# JTAG.net
KiCad netlist of a schematic drawn in Altium Designer
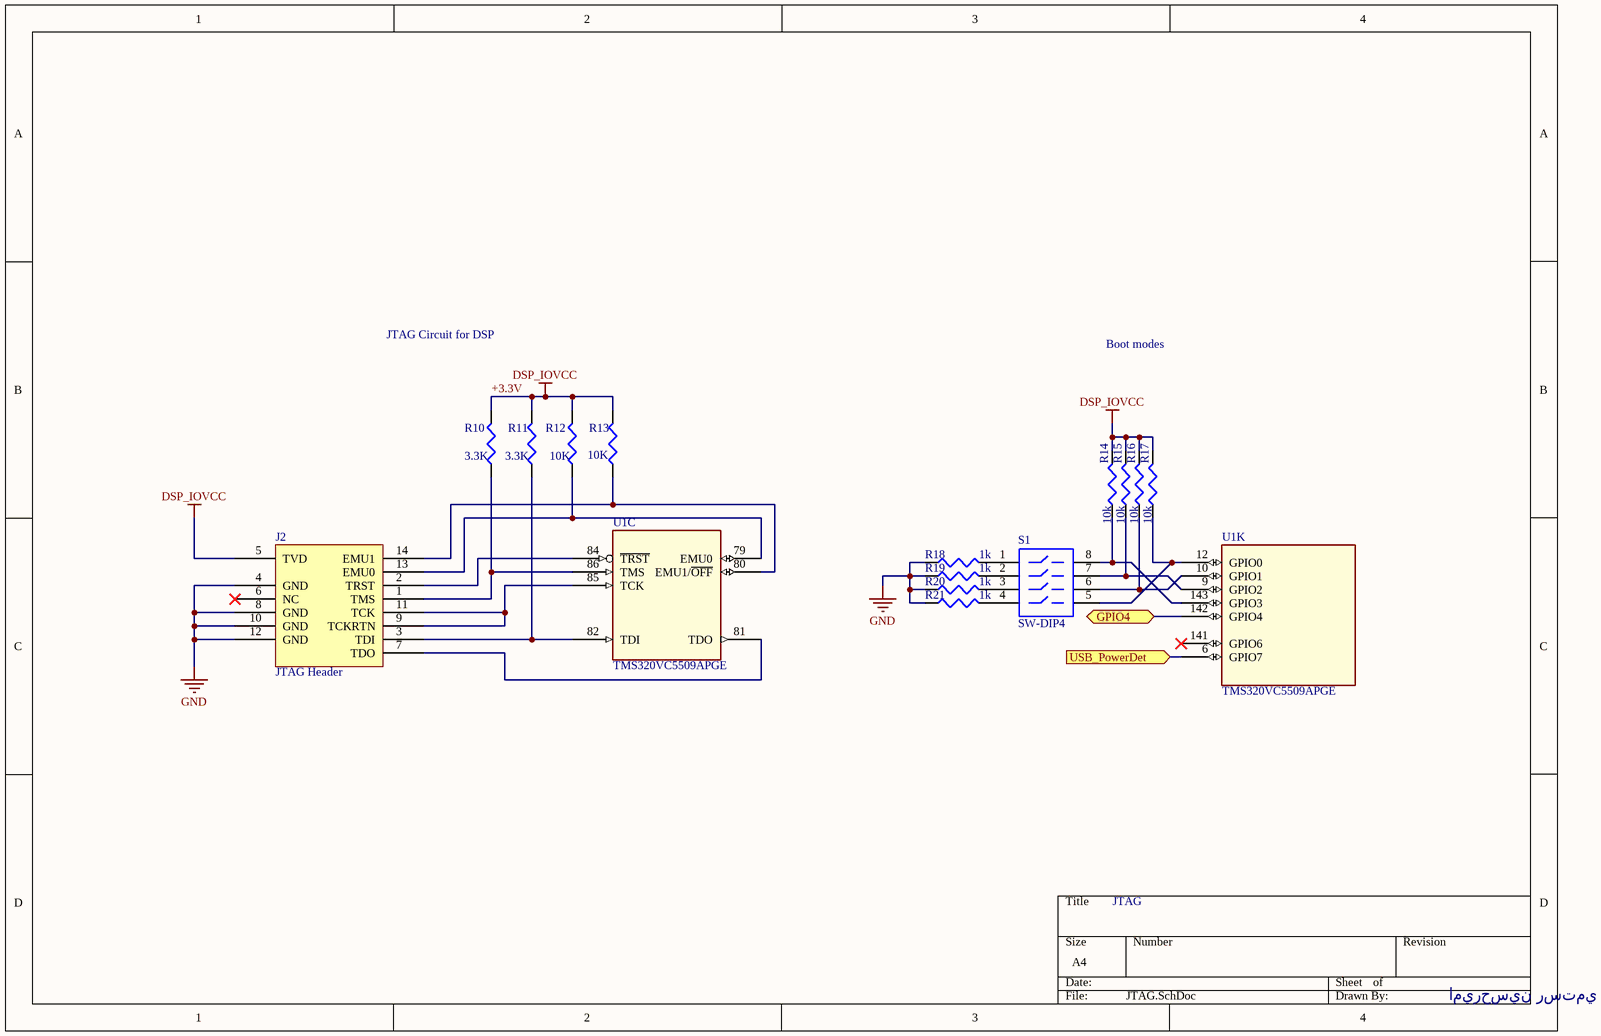
[diagram p0: JTAG.SchDoc]

(export (version "E")
  (design (tool "Eeschema 10.0.6"))
  (components
    (comp (ref "J2")
      (value "JTAG Header")
      (footprint "HDR2X7")
      (description "JTAG Header for DSP 5509")
      (libsource (lib "JTAG_Header") (part "JTAG Header"))
    )
    (comp (ref "R10")
      (value "3.3K")
      (footprint "J1-0603")
      (description "Resistor")
      (fields (field (name "Comment") "3.3k") (field (name "PUBLISHER") "Altium Limited"))
      (libsource (lib "Miscellaneous Devices") (part "Res3"))
    )
    (comp (ref "R11")
      (value "3.3K")
      (footprint "J1-0603")
      (description "Resistor")
      (fields (field (name "Comment") "3.3k") (field (name "PUBLISHER") "Altium Limited"))
      (libsource (lib "Miscellaneous Devices") (part "Res3"))
    )
    (comp (ref "R12")
      (value "10K")
      (footprint "J1-0603")
      (description "Resistor")
      (fields (field (name "Comment") "10k") (field (name "PUBLISHER") "Altium Limited"))
      (libsource (lib "Miscellaneous Devices") (part "Res3"))
    )
    (comp (ref "R13")
      (value "10K")
      (footprint "J1-0603")
      (description "Resistor")
      (fields (field (name "Comment") "10k") (field (name "PUBLISHER") "Altium Limited"))
      (libsource (lib "Miscellaneous Devices") (part "Res3"))
    )
    (comp (ref "R14")
      (value "10k")
      (footprint "J1-0603")
      (description "Resistor")
      (fields (field (name "PUBLISHER") "Altium Limited"))
      (libsource (lib "Miscellaneous Devices") (part "Res3"))
    )
    (comp (ref "R15")
      (value "10k")
      (footprint "J1-0603")
      (description "Resistor")
      (fields (field (name "PUBLISHER") "Altium Limited"))
      (libsource (lib "Miscellaneous Devices") (part "Res3"))
    )
    (comp (ref "R16")
      (value "10k")
      (footprint "J1-0603")
      (description "Resistor")
      (fields (field (name "PUBLISHER") "Altium Limited"))
      (libsource (lib "Miscellaneous Devices") (part "Res3"))
    )
    (comp (ref "R17")
      (value "10k")
      (footprint "J1-0603")
      (description "Resistor")
      (fields (field (name "PUBLISHER") "Altium Limited"))
      (libsource (lib "Miscellaneous Devices") (part "Res3"))
    )
    (comp (ref "R18")
      (value "1k")
      (footprint "J1-0603")
      (description "Resistor")
      (fields (field (name "PUBLISHER") "Altium Limited"))
      (libsource (lib "Miscellaneous Devices") (part "Res3"))
    )
    (comp (ref "R19")
      (value "1k")
      (footprint "J1-0603")
      (description "Resistor")
      (fields (field (name "PUBLISHER") "Altium Limited"))
      (libsource (lib "Miscellaneous Devices") (part "Res3"))
    )
    (comp (ref "R20")
      (value "1k")
      (footprint "J1-0603")
      (description "Resistor")
      (fields (field (name "PUBLISHER") "Altium Limited"))
      (libsource (lib "Miscellaneous Devices") (part "Res3"))
    )
    (comp (ref "R21")
      (value "1k")
      (footprint "J1-0603")
      (description "Resistor")
      (fields (field (name "PUBLISHER") "Altium Limited"))
      (libsource (lib "Miscellaneous Devices") (part "Res3"))
    )
    (comp (ref "S1")
      (value "SW-DIP4")
      (footprint "DIP-8")
      (description "DIP Switch")
      (fields (field (name "PUBLISHER") "Altium Limited"))
      (libsource (lib "Miscellaneous Devices") (part "SW-DIP4"))
    )
    (comp (ref "U1")
      (value "TMS320VC5509APGE")
      (footprint "TMSVC5509APGA")
      (libsource (lib "TMSVC5509APGE") (part "TMS320VC5509APGE"))
    )
  )
  (nets
    (net (code "1") (name "/GPIO4") (class "Default")
      (node (ref "U1") (pin "142") (pinfunction "GPIO4_142") (pintype "bidirectional"))
    )
    (net (code "2") (name "/USB_PowerDet") (class "Default")
      (node (ref "U1") (pin "6") (pinfunction "GPIO7_6") (pintype "bidirectional"))
    )
    (net (code "3") (name "DSP_IOVCC") (class "Default")
      (node (ref "J2") (pin "5") (pinfunction "TVD_5") (pintype "passive"))
      (node (ref "R10") (pin "2") (pinfunction "2_2") (pintype "passive"))
      (node (ref "R11") (pin "2") (pinfunction "2_2") (pintype "passive"))
      (node (ref "R12") (pin "2") (pinfunction "2_2") (pintype "passive"))
      (node (ref "R13") (pin "2") (pinfunction "2_2") (pintype "passive"))
      (node (ref "R14") (pin "2") (pinfunction "2_2") (pintype "passive"))
      (node (ref "R15") (pin "2") (pinfunction "2_2") (pintype "passive"))
      (node (ref "R16") (pin "2") (pinfunction "2_2") (pintype "passive"))
      (node (ref "R17") (pin "2") (pinfunction "2_2") (pintype "passive"))
    )
    (net (code "4") (name "GND") (class "Default")
      (node (ref "J2") (pin "10") (pinfunction "GND_10") (pintype "passive"))
      (node (ref "J2") (pin "12") (pinfunction "GND_12") (pintype "passive"))
      (node (ref "J2") (pin "4") (pinfunction "GND_4") (pintype "passive"))
      (node (ref "J2") (pin "8") (pinfunction "GND_8") (pintype "passive"))
      (node (ref "R18") (pin "1") (pinfunction "1_1") (pintype "passive"))
      (node (ref "R19") (pin "1") (pinfunction "1_1") (pintype "passive"))
      (node (ref "R20") (pin "1") (pinfunction "1_1") (pintype "passive"))
      (node (ref "R21") (pin "1") (pinfunction "1_1") (pintype "passive"))
    )
    (net (code "5") (name "Net-(J2-EMU0)") (class "Default")
      (node (ref "J2") (pin "13") (pinfunction "EMU0_13") (pintype "passive"))
      (node (ref "R12") (pin "1") (pinfunction "1_1") (pintype "passive"))
      (node (ref "U1") (pin "79") (pinfunction "EMU0_79") (pintype "bidirectional"))
    )
    (net (code "6") (name "Net-(J2-EMU1)") (class "Default")
      (node (ref "J2") (pin "14") (pinfunction "EMU1_14") (pintype "passive"))
      (node (ref "R13") (pin "1") (pinfunction "1_1") (pintype "passive"))
      (node (ref "U1") (pin "80") (pinfunction "EMU1/~{OFF}_80") (pintype "bidirectional"))
    )
    (net (code "7") (name "Net-(J2-TCK)") (class "Default")
      (node (ref "J2") (pin "11") (pinfunction "TCK_11") (pintype "passive"))
      (node (ref "J2") (pin "9") (pinfunction "TCKRTN_9") (pintype "passive"))
      (node (ref "U1") (pin "85") (pinfunction "TCK_85") (pintype "input"))
    )
    (net (code "8") (name "Net-(J2-TDI)") (class "Default")
      (node (ref "J2") (pin "3") (pinfunction "TDI_3") (pintype "passive"))
      (node (ref "R11") (pin "1") (pinfunction "1_1") (pintype "passive"))
      (node (ref "U1") (pin "82") (pinfunction "TDI_82") (pintype "input"))
    )
    (net (code "9") (name "Net-(J2-TDO)") (class "Default")
      (node (ref "J2") (pin "7") (pinfunction "TDO_7") (pintype "passive"))
      (node (ref "U1") (pin "81") (pinfunction "TDO_81") (pintype "output"))
    )
    (net (code "10") (name "Net-(J2-TMS)") (class "Default")
      (node (ref "J2") (pin "1") (pinfunction "TMS_1") (pintype "passive"))
      (node (ref "R10") (pin "1") (pinfunction "1_1") (pintype "passive"))
      (node (ref "U1") (pin "86") (pinfunction "TMS_86") (pintype "input"))
    )
    (net (code "11") (name "Net-(J2-TRST)") (class "Default")
      (node (ref "J2") (pin "2") (pinfunction "TRST_2") (pintype "passive"))
      (node (ref "U1") (pin "84") (pinfunction "~{TRST}_84") (pintype "input"))
    )
    (net (code "12") (name "Net-(R18-Pad2)") (class "Default")
      (node (ref "R18") (pin "2") (pinfunction "2_2") (pintype "passive"))
      (node (ref "S1") (pin "1") (pinfunction "1_1") (pintype "passive"))
    )
    (net (code "13") (name "Net-(R19-Pad2)") (class "Default")
      (node (ref "R19") (pin "2") (pinfunction "2_2") (pintype "passive"))
      (node (ref "S1") (pin "2") (pinfunction "2_2") (pintype "passive"))
    )
    (net (code "14") (name "Net-(R20-Pad2)") (class "Default")
      (node (ref "R20") (pin "2") (pinfunction "2_2") (pintype "passive"))
      (node (ref "S1") (pin "3") (pinfunction "3_3") (pintype "passive"))
    )
    (net (code "15") (name "Net-(R21-Pad2)") (class "Default")
      (node (ref "R21") (pin "2") (pinfunction "2_2") (pintype "passive"))
      (node (ref "S1") (pin "4") (pinfunction "4_4") (pintype "passive"))
    )
    (net (code "16") (name "Net-(U1K-GPIO0)") (class "Default")
      (node (ref "R17") (pin "1") (pinfunction "1_1") (pintype "passive"))
      (node (ref "S1") (pin "5") (pinfunction "5_5") (pintype "passive"))
      (node (ref "U1") (pin "12") (pinfunction "GPIO0_12") (pintype "bidirectional"))
    )
    (net (code "17") (name "Net-(U1K-GPIO1)") (class "Default")
      (node (ref "R16") (pin "1") (pinfunction "1_1") (pintype "passive"))
      (node (ref "S1") (pin "6") (pinfunction "6_6") (pintype "passive"))
      (node (ref "U1") (pin "10") (pinfunction "GPIO1_10") (pintype "bidirectional"))
    )
    (net (code "18") (name "Net-(U1K-GPIO2)") (class "Default")
      (node (ref "R15") (pin "1") (pinfunction "1_1") (pintype "passive"))
      (node (ref "S1") (pin "7") (pinfunction "7_7") (pintype "passive"))
      (node (ref "U1") (pin "9") (pinfunction "GPIO2_9") (pintype "bidirectional"))
    )
    (net (code "19") (name "Net-(U1K-GPIO3)") (class "Default")
      (node (ref "R14") (pin "1") (pinfunction "1_1") (pintype "passive"))
      (node (ref "S1") (pin "8") (pinfunction "8_8") (pintype "passive"))
      (node (ref "U1") (pin "143") (pinfunction "GPIO3_143") (pintype "bidirectional"))
    )
    (net (code "20") (name "unconnected-(J2-NC-Pad6)") (class "Default")
      (node (ref "J2") (pin "6") (pinfunction "NC_6") (pintype "passive+no_connect"))
    )
    (net (code "21") (name "unconnected-(U1K-GPIO6-Pad141)") (class "Default")
      (node (ref "U1") (pin "141") (pinfunction "GPIO6_141") (pintype "bidirectional+no_connect"))
    )
  )
)
